# EXPS2_ISP.net
KiCad netlist of a schematic drawn in EAGLE
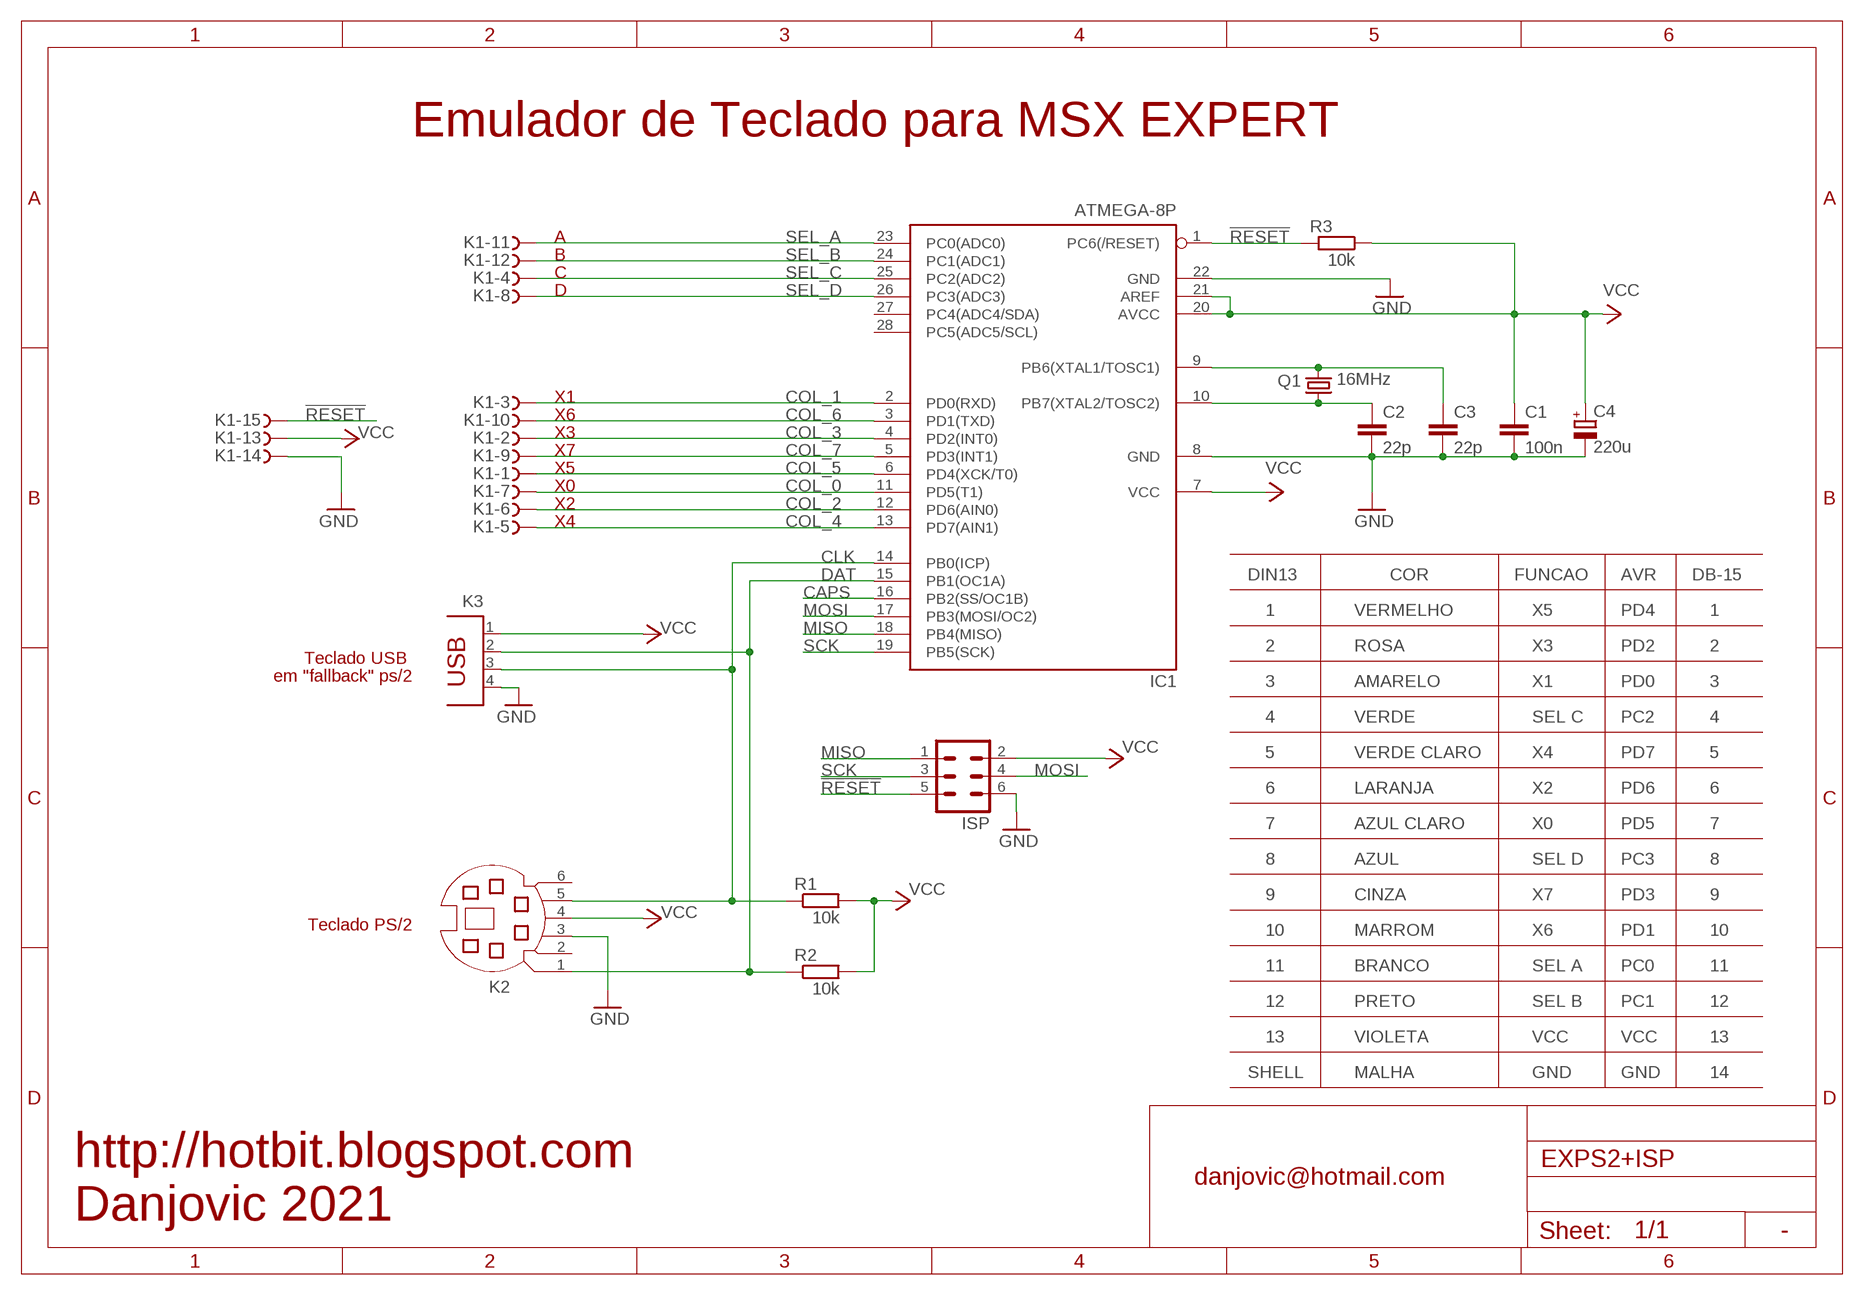
[diagram p0: schematic, sheet 1]

(export (version "E")
  (design (tool "Eeschema 10.0.6"))
  (components
    (comp (ref "C1")
      (value "100n")
      (footprint "eagle-import:C050-024X044")
      (libsource (lib "eagle-import") (part "C-EU050-024X044"))
    )
    (comp (ref "C2")
      (value "22p")
      (footprint "eagle-import:C050-024X044")
      (libsource (lib "eagle-import") (part "C-EU050-024X044"))
    )
    (comp (ref "C3")
      (value "22p")
      (footprint "eagle-import:C050-024X044")
      (libsource (lib "eagle-import") (part "C-EU050-024X044"))
    )
    (comp (ref "C4")
      (value "220u")
      (footprint "eagle-import:E2,5-6")
      (libsource (lib "eagle-import") (part "CPOL-EUE2.5-6"))
    )
    (comp (ref "IC1")
      (value "ATMEGA-8P")
      (footprint "eagle-import:DIL28-3")
      (libsource (lib "eagle-import") (part "MEGA8-P"))
    )
    (comp (ref "ISP")
      (value "ML6")
      (footprint "eagle-import:ML6")
      (libsource (lib "eagle-import") (part "ML6"))
    )
    (comp (ref "K1")
      (value "F15HPS")
      (footprint "eagle-import:F15HP")
      (libsource (lib "eagle-import") (part "F15?SHP"))
    )
    (comp (ref "K2")
      (value "MD06SS")
      (footprint "eagle-import:MDIN06SS")
      (libsource (lib "eagle-import") (part "MD06SS"))
    )
    (comp (ref "K3")
      (value "PN87520")
      (footprint "eagle-import:PN87520")
      (libsource (lib "eagle-import") (part "PN87520"))
    )
    (comp (ref "Q1")
      (value "16MHz")
      (footprint "eagle-import:HC49U-V")
      (libsource (lib "eagle-import") (part "CRYSTALHC49U-V"))
    )
    (comp (ref "R1")
      (value "10k")
      (footprint "eagle-import:0204_5")
      (libsource (lib "eagle-import") (part "R-EU_0204/5"))
    )
    (comp (ref "R2")
      (value "10k")
      (footprint "eagle-import:0204_5")
      (libsource (lib "eagle-import") (part "R-EU_0204/5"))
    )
    (comp (ref "R3")
      (value "10k")
      (footprint "eagle-import:0204_5")
      (libsource (lib "eagle-import") (part "R-EU_0204/5"))
    )
  )
  (nets
    (net (code "1") (name "/CLK") (class "Default")
      (node (ref "IC1") (pin "14") (pinfunction "PB0(ICP)_14") (pintype "bidirectional"))
      (node (ref "K2") (pin "5") (pinfunction "5_5") (pintype "passive"))
      (node (ref "K3") (pin "3") (pinfunction "3_3") (pintype "passive"))
      (node (ref "R1") (pin "1") (pinfunction "1_1") (pintype "passive"))
    )
    (net (code "2") (name "/COL_0") (class "Default")
      (node (ref "IC1") (pin "11") (pinfunction "PD5(T1)_11") (pintype "bidirectional"))
      (node (ref "K1") (pin "7") (pinfunction "F_7") (pintype "passive"))
    )
    (net (code "3") (name "/COL_1") (class "Default")
      (node (ref "IC1") (pin "2") (pinfunction "PD0(RXD)_2") (pintype "bidirectional"))
      (node (ref "K1") (pin "3") (pinfunction "F_3") (pintype "passive"))
    )
    (net (code "4") (name "/COL_2") (class "Default")
      (node (ref "IC1") (pin "12") (pinfunction "PD6(AIN0)_12") (pintype "bidirectional"))
      (node (ref "K1") (pin "6") (pinfunction "F_6") (pintype "passive"))
    )
    (net (code "5") (name "/COL_3") (class "Default")
      (node (ref "IC1") (pin "4") (pinfunction "PD2(INT0)_4") (pintype "bidirectional"))
      (node (ref "K1") (pin "2") (pinfunction "F_2") (pintype "passive"))
    )
    (net (code "6") (name "/COL_4") (class "Default")
      (node (ref "IC1") (pin "13") (pinfunction "PD7(AIN1)_13") (pintype "bidirectional"))
      (node (ref "K1") (pin "5") (pinfunction "F_5") (pintype "passive"))
    )
    (net (code "7") (name "/COL_5") (class "Default")
      (node (ref "IC1") (pin "6") (pinfunction "PD4(XCK/T0)_6") (pintype "bidirectional"))
      (node (ref "K1") (pin "1") (pinfunction "F_1") (pintype "passive"))
    )
    (net (code "8") (name "/COL_6") (class "Default")
      (node (ref "IC1") (pin "3") (pinfunction "PD1(TXD)_3") (pintype "bidirectional"))
      (node (ref "K1") (pin "10") (pinfunction "F_10") (pintype "passive"))
    )
    (net (code "9") (name "/COL_7") (class "Default")
      (node (ref "IC1") (pin "5") (pinfunction "PD3(INT1)_5") (pintype "bidirectional"))
      (node (ref "K1") (pin "9") (pinfunction "F_9") (pintype "passive"))
    )
    (net (code "10") (name "/DAT") (class "Default")
      (node (ref "IC1") (pin "15") (pinfunction "PB1(OC1A)_15") (pintype "bidirectional"))
      (node (ref "K2") (pin "1") (pinfunction "1_1") (pintype "passive"))
      (node (ref "K3") (pin "2") (pinfunction "2_2") (pintype "passive"))
      (node (ref "R2") (pin "1") (pinfunction "1_1") (pintype "passive"))
    )
    (net (code "11") (name "/MISO") (class "Default")
      (node (ref "IC1") (pin "18") (pinfunction "PB4(MISO)_18") (pintype "bidirectional"))
      (node (ref "ISP") (pin "1") (pinfunction "1_1") (pintype "passive"))
    )
    (net (code "12") (name "/MOSI") (class "Default")
      (node (ref "IC1") (pin "17") (pinfunction "PB3(MOSI/OC2)_17") (pintype "bidirectional"))
      (node (ref "ISP") (pin "4") (pinfunction "4_4") (pintype "passive"))
    )
    (net (code "13") (name "/SCK") (class "Default")
      (node (ref "IC1") (pin "19") (pinfunction "PB5(SCK)_19") (pintype "bidirectional"))
      (node (ref "ISP") (pin "3") (pinfunction "3_3") (pintype "passive"))
    )
    (net (code "14") (name "/SEL_A") (class "Default")
      (node (ref "IC1") (pin "23") (pinfunction "PC0(ADC0)_23") (pintype "bidirectional"))
      (node (ref "K1") (pin "11") (pinfunction "F_11") (pintype "passive"))
    )
    (net (code "15") (name "/SEL_B") (class "Default")
      (node (ref "IC1") (pin "24") (pinfunction "PC1(ADC1)_24") (pintype "bidirectional"))
      (node (ref "K1") (pin "12") (pinfunction "F_12") (pintype "passive"))
    )
    (net (code "16") (name "/SEL_C") (class "Default")
      (node (ref "IC1") (pin "25") (pinfunction "PC2(ADC2)_25") (pintype "bidirectional"))
      (node (ref "K1") (pin "4") (pinfunction "F_4") (pintype "passive"))
    )
    (net (code "17") (name "/SEL_D") (class "Default")
      (node (ref "IC1") (pin "26") (pinfunction "PC3(ADC3)_26") (pintype "bidirectional"))
      (node (ref "K1") (pin "8") (pinfunction "F_8") (pintype "passive"))
    )
    (net (code "18") (name "/~{RESET}") (class "Default")
      (node (ref "IC1") (pin "1") (pinfunction "PC6(/RESET)_1") (pintype "bidirectional"))
      (node (ref "ISP") (pin "5") (pinfunction "5_5") (pintype "passive"))
      (node (ref "K1") (pin "15") (pinfunction "F_15") (pintype "passive"))
      (node (ref "R3") (pin "2") (pinfunction "2_2") (pintype "passive"))
    )
    (net (code "19") (name "GND") (class "Default")
      (node (ref "C1") (pin "2") (pinfunction "2_2") (pintype "passive"))
      (node (ref "C2") (pin "2") (pinfunction "2_2") (pintype "passive"))
      (node (ref "C3") (pin "2") (pinfunction "2_2") (pintype "passive"))
      (node (ref "C4") (pin "-") (pinfunction "-_-") (pintype "passive"))
      (node (ref "IC1") (pin "22") (pinfunction "GND_22") (pintype "power_in"))
      (node (ref "IC1") (pin "8") (pinfunction "GND_8") (pintype "power_in"))
      (node (ref "ISP") (pin "6") (pinfunction "6_6") (pintype "passive"))
      (node (ref "K1") (pin "14") (pinfunction "F_14") (pintype "passive"))
      (node (ref "K2") (pin "3") (pinfunction "3_3") (pintype "passive"))
      (node (ref "K3") (pin "4") (pinfunction "4_4") (pintype "passive"))
    )
    (net (code "20") (name "Net-(IC1-PB6(XTAL1{slash}TOSC1))") (class "Default")
      (node (ref "C3") (pin "1") (pinfunction "1_1") (pintype "passive"))
      (node (ref "IC1") (pin "9") (pinfunction "PB6(XTAL1/TOSC1)_9") (pintype "bidirectional"))
      (node (ref "Q1") (pin "2") (pinfunction "2_2") (pintype "passive"))
    )
    (net (code "21") (name "Net-(IC1-PB7(XTAL2{slash}TOSC2))") (class "Default")
      (node (ref "C2") (pin "1") (pinfunction "1_1") (pintype "passive"))
      (node (ref "IC1") (pin "10") (pinfunction "PB7(XTAL2/TOSC2)_10") (pintype "bidirectional"))
      (node (ref "Q1") (pin "1") (pinfunction "1_1") (pintype "passive"))
    )
    (net (code "22") (name "VCC") (class "Default")
      (node (ref "C1") (pin "1") (pinfunction "1_1") (pintype "passive"))
      (node (ref "C4") (pin "+") (pinfunction "+_+") (pintype "passive"))
      (node (ref "IC1") (pin "20") (pinfunction "AVCC_20") (pintype "power_in"))
      (node (ref "IC1") (pin "21") (pinfunction "AREF_21") (pintype "passive"))
      (node (ref "IC1") (pin "7") (pinfunction "VCC_7") (pintype "power_in"))
      (node (ref "ISP") (pin "2") (pinfunction "2_2") (pintype "passive"))
      (node (ref "K1") (pin "13") (pinfunction "F_13") (pintype "passive"))
      (node (ref "K2") (pin "4") (pinfunction "4_4") (pintype "passive"))
      (node (ref "K3") (pin "1") (pinfunction "1_1") (pintype "passive"))
      (node (ref "R1") (pin "2") (pinfunction "2_2") (pintype "passive"))
      (node (ref "R2") (pin "2") (pinfunction "2_2") (pintype "passive"))
      (node (ref "R3") (pin "1") (pinfunction "1_1") (pintype "passive"))
    )
    (net (code "23") (name "unconnected-(IC1-PB2(SS{slash}OC1B)-Pad16)") (class "Default")
      (node (ref "IC1") (pin "16") (pinfunction "PB2(SS/OC1B)_16") (pintype "bidirectional"))
    )
    (net (code "24") (name "unconnected-(IC1-PC4(ADC4{slash}SDA)-Pad27)") (class "Default")
      (node (ref "IC1") (pin "27") (pinfunction "PC4(ADC4/SDA)_27") (pintype "bidirectional"))
    )
    (net (code "25") (name "unconnected-(IC1-PC5(ADC5{slash}SCL)-Pad28)") (class "Default")
      (node (ref "IC1") (pin "28") (pinfunction "PC5(ADC5/SCL)_28") (pintype "bidirectional"))
    )
    (net (code "26") (name "unconnected-(K2-Pad2)") (class "Default")
      (node (ref "K2") (pin "2") (pinfunction "2_2") (pintype "passive"))
    )
    (net (code "27") (name "unconnected-(K2-Pad6)") (class "Default")
      (node (ref "K2") (pin "6") (pinfunction "6_6") (pintype "passive"))
    )
  )
)
